# DebugBreakout_RevD.net
KiCad netlist of a schematic drawn in Altium Designer
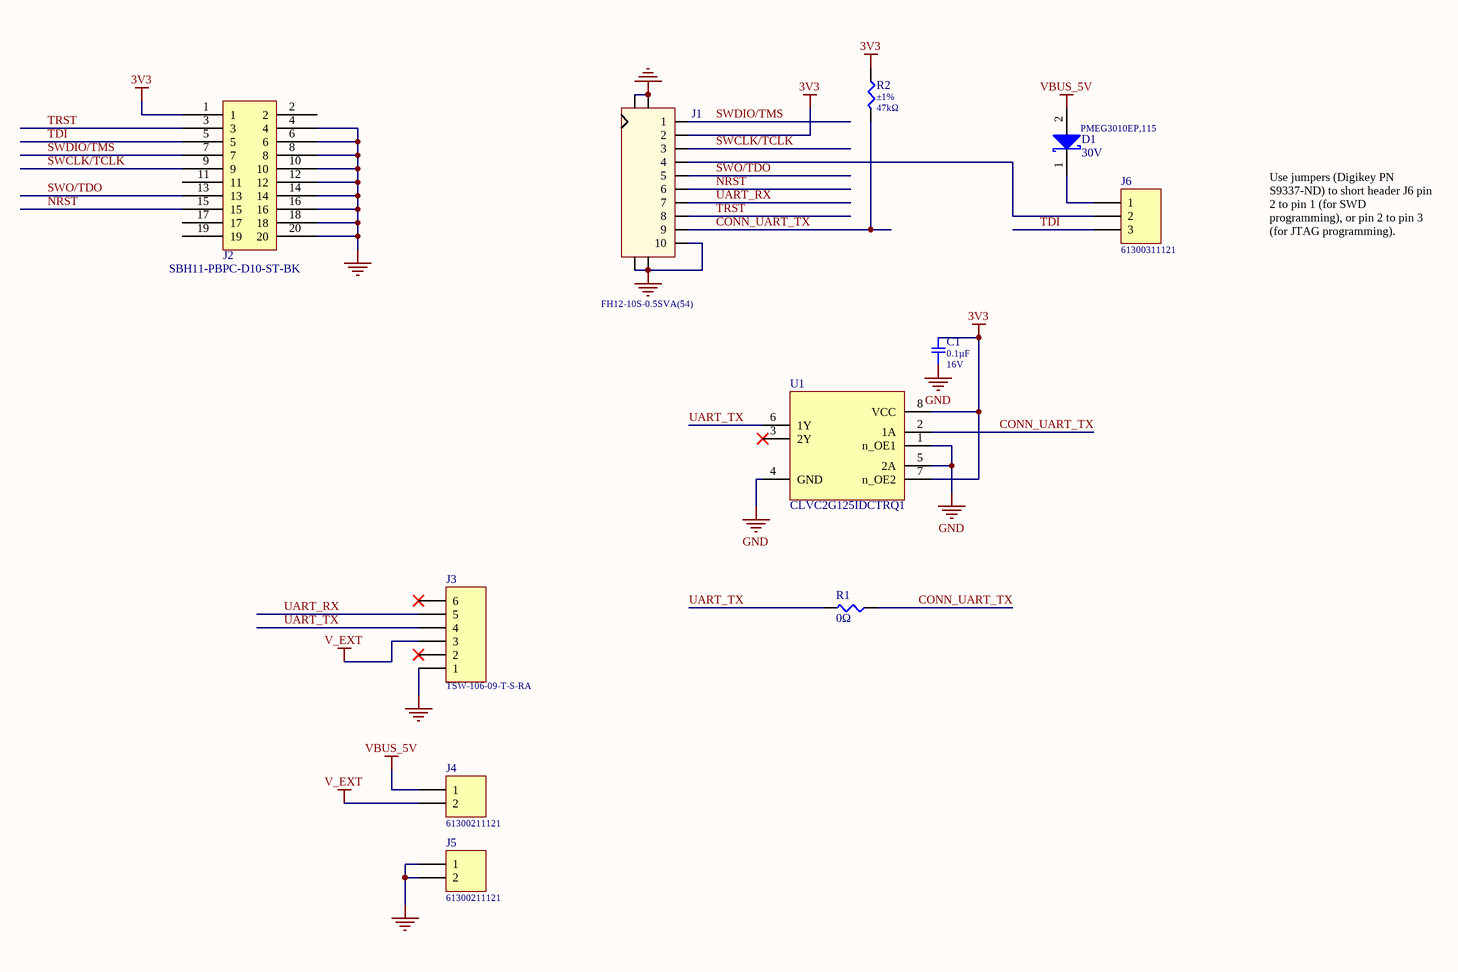
[diagram p0: DebugBreakout_RevD.SchDoc]

(export (version "E")
  (design (tool "Eeschema 10.0.6"))
  (components
    (comp (ref "C1")
      (value "0.1µF")
      (footprint "CAP-0402")
      (description "CAP CER 0.1UF 16V X7R 0402 5%")
      (fields
        (field (name "MANUFACTURER") "Murata")
        (field (name "MPN") "GRM155R71C104JA88D")
        (field (name "VOLTAGE RATING") "16V")
      )
      (libsource (lib "capacitors") (part "CAP-0.1uF-16V-0402"))
    )
    (comp (ref "D1")
      (value "PMEG3010EP,115")
      (footprint "DIODE-SOD128")
      (description "DIODE SCHOTTKY 30V 1A SOD128")
      (fields (field (name "BASE PART NUMBER") "PMEG3010") (field (name "REVERSE VOLTAGE") "30V"))
      (libsource (lib "diodes") (part "DIODE-SCHOTTKY-30V-1A-SOD128"))
    )
    (comp (ref "J1")
      (value "FH12-10S-0.5SVA(54)")
      (footprint "CONN-V-FPC-10P FH12-10S-0.5SVA(54)")
      (description "CONN FFC VERT 10POS 0.50MM SMD")
      (libsource (lib "msx") (part "CONN-V-FPC-10P-0.5MM"))
    )
    (comp (ref "J2")
      (value "SBH11-PBPC-D10-ST-BK")
      (footprint "HDR-V-2x10-KEYED")
      (description "CONN HEADER VERT 20POS 2.54MM")
      (libsource (lib "headers") (part "HDR-V-2x10-M"))
    )
    (comp (ref "J3")
      (value "TSW-106-09-T-S-RA")
      (footprint "HDR-RA-1X6")
      (description "Conn Unshrouded Header HDR 6 POS 2.54mm Solder RA Thru-Hole Automotive Bulk")
      (libsource (lib "headers") (part "HDR-RA-1X6-M"))
    )
    (comp (ref "J4")
      (value "61300211121")
      (footprint "HDR-V-1X2")
      (description "Header, 2-Pin, 0.1\"")
      (fields (field (name "MANUFACTURER") "Wurth Electronics") (field (name "PUBLISHER") "Altium Limited"))
      (libsource (lib "headers") (part "HDR-V-1X2-M"))
    )
    (comp (ref "J5")
      (value "61300211121")
      (footprint "HDR-V-1X2")
      (description "Header, 2-Pin, 0.1\"")
      (fields (field (name "MANUFACTURER") "Wurth Electronics") (field (name "PUBLISHER") "Altium Limited"))
      (libsource (lib "headers") (part "HDR-V-1X2-M"))
    )
    (comp (ref "J6")
      (value "61300311121")
      (footprint "HDR-V-1X3")
      (description "Header, 3-Pin, 0.1\"")
      (fields (field (name "MANUFACTURER") "Wurth Electronics") (field (name "PUBLISHER") "Altium Limited"))
      (libsource (lib "headers") (part "HDR-V-1X3-M"))
    )
    (comp (ref "R1")
      (value "0Ω")
      (footprint "RES-0402")
      (description "RES 0 OHM JUMPER 1/16W 0402")
      (fields
        (field (name "MANUFACTURER") "Yageo")
        (field (name "MANUFACTURER PART NUMBER") "RC0402FR-070RL")
      )
      (libsource (lib "resistors") (part "RES-0-0402"))
    )
    (comp (ref "R2")
      (value "47kΩ")
      (footprint "RES-0402")
      (description "RES SMD 47K OHM 1% 1/16W 0402")
      (fields (field (name "TOLERANCE") "±1%") (field (name "Comment") "RC0402FR-0747KL"))
      (libsource (lib "resistors") (part "RES-47K-0402"))
    )
    (comp (ref "U1")
      (value "CLVC2G125IDCTRQ1")
      (footprint "IC-MSOP-8P")
      (description "5.5 V SMT Dual Buffer Gate with 3-State Outputs - SM8")
      (libsource (lib "chagan") (part "IC-CLVC2G125I"))
    )
  )
  (nets
    (net (code "1") (name "/CONN_UART_TX") (class "Default")
      (node (ref "J1") (pin "9") (pinfunction "9_9") (pintype "passive"))
      (node (ref "R1") (pin "1") (pinfunction "1_1") (pintype "passive"))
      (node (ref "R2") (pin "2") (pinfunction "2_2") (pintype "passive"))
      (node (ref "U1") (pin "2") (pinfunction "1A_2") (pintype "passive"))
    )
    (net (code "2") (name "/NRST") (class "Default")
      (node (ref "J1") (pin "6") (pinfunction "6_6") (pintype "passive"))
      (node (ref "J2") (pin "15") (pinfunction "15_15") (pintype "power_in"))
    )
    (net (code "3") (name "/SWCLK{slash}TCLK") (class "Default")
      (node (ref "J1") (pin "3") (pinfunction "3_3") (pintype "passive"))
      (node (ref "J2") (pin "9") (pinfunction "9_9") (pintype "passive"))
    )
    (net (code "4") (name "/SWDIO{slash}TMS") (class "Default")
      (node (ref "J1") (pin "1") (pinfunction "1_1") (pintype "passive"))
      (node (ref "J2") (pin "7") (pinfunction "7_7") (pintype "passive"))
    )
    (net (code "5") (name "/SWO{slash}TDO") (class "Default")
      (node (ref "J1") (pin "5") (pinfunction "5_5") (pintype "passive"))
      (node (ref "J2") (pin "13") (pinfunction "13_13") (pintype "power_in"))
    )
    (net (code "6") (name "/TDI") (class "Default")
      (node (ref "J2") (pin "5") (pinfunction "5_5") (pintype "passive"))
      (node (ref "J6") (pin "3") (pinfunction "3_3") (pintype "passive"))
    )
    (net (code "7") (name "/TRST") (class "Default")
      (node (ref "J1") (pin "8") (pinfunction "8_8") (pintype "passive"))
      (node (ref "J2") (pin "3") (pinfunction "3_3") (pintype "passive"))
    )
    (net (code "8") (name "/UART_RX") (class "Default")
      (node (ref "J1") (pin "7") (pinfunction "7_7") (pintype "passive"))
      (node (ref "J3") (pin "5") (pinfunction "5_5") (pintype "passive"))
    )
    (net (code "9") (name "/UART_TX") (class "Default")
      (node (ref "J3") (pin "4") (pinfunction "4_4") (pintype "passive"))
      (node (ref "R1") (pin "2") (pinfunction "2_2") (pintype "passive"))
      (node (ref "U1") (pin "6") (pinfunction "1Y_6") (pintype "passive"))
    )
    (net (code "10") (name "3V3") (class "Default")
      (node (ref "C1") (pin "2") (pinfunction "2_2") (pintype "passive"))
      (node (ref "J1") (pin "2") (pinfunction "2_2") (pintype "passive"))
      (node (ref "J2") (pin "1") (pinfunction "1_1") (pintype "passive"))
      (node (ref "R2") (pin "1") (pinfunction "1_1") (pintype "passive"))
      (node (ref "U1") (pin "7") (pinfunction "n_OE2_7") (pintype "passive"))
      (node (ref "U1") (pin "8") (pinfunction "VCC_8") (pintype "passive"))
    )
    (net (code "11") (name "GND") (class "Default")
      (node (ref "C1") (pin "1") (pinfunction "1_1") (pintype "passive"))
      (node (ref "J1") (pin "10") (pinfunction "10_10") (pintype "passive"))
      (node (ref "J1") (pin "ME1") (pinfunction "ME1_ME1") (pintype "passive"))
      (node (ref "J1") (pin "ME2") (pinfunction "ME2_ME2") (pintype "passive"))
      (node (ref "J1") (pin "ME3") (pinfunction "ME3_ME3") (pintype "passive"))
      (node (ref "J1") (pin "ME4") (pinfunction "ME4_ME4") (pintype "passive"))
      (node (ref "J2") (pin "10") (pinfunction "10_10") (pintype "passive"))
      (node (ref "J2") (pin "12") (pinfunction "12_12") (pintype "power_in"))
      (node (ref "J2") (pin "14") (pinfunction "14_14") (pintype "power_in"))
      (node (ref "J2") (pin "16") (pinfunction "16_16") (pintype "power_in"))
      (node (ref "J2") (pin "18") (pinfunction "18_18") (pintype "power_in"))
      (node (ref "J2") (pin "20") (pinfunction "20_20") (pintype "power_in"))
      (node (ref "J2") (pin "4") (pinfunction "4_4") (pintype "passive"))
      (node (ref "J2") (pin "6") (pinfunction "6_6") (pintype "passive"))
      (node (ref "J2") (pin "8") (pinfunction "8_8") (pintype "passive"))
      (node (ref "J3") (pin "1") (pinfunction "1_1") (pintype "passive"))
      (node (ref "J5") (pin "1") (pinfunction "1_1") (pintype "passive"))
      (node (ref "J5") (pin "2") (pinfunction "2_2") (pintype "passive"))
      (node (ref "U1") (pin "1") (pinfunction "n_OE1_1") (pintype "passive"))
      (node (ref "U1") (pin "4") (pinfunction "GND_4") (pintype "passive"))
      (node (ref "U1") (pin "5") (pinfunction "2A_5") (pintype "passive"))
    )
    (net (code "12") (name "Net-(D1-K)") (class "Default")
      (node (ref "D1") (pin "1") (pinfunction "K_1") (pintype "passive"))
      (node (ref "J6") (pin "1") (pinfunction "1_1") (pintype "passive"))
    )
    (net (code "13") (name "Net-(J1-Pad4)") (class "Default")
      (node (ref "J1") (pin "4") (pinfunction "4_4") (pintype "passive"))
      (node (ref "J6") (pin "2") (pinfunction "2_2") (pintype "passive"))
    )
    (net (code "14") (name "VBUS_5V") (class "Default")
      (node (ref "D1") (pin "2") (pinfunction "A_2") (pintype "passive"))
      (node (ref "J4") (pin "1") (pinfunction "1_1") (pintype "passive"))
    )
    (net (code "15") (name "V_EXT") (class "Default")
      (node (ref "J3") (pin "3") (pinfunction "3_3") (pintype "passive"))
      (node (ref "J4") (pin "2") (pinfunction "2_2") (pintype "passive"))
    )
    (net (code "16") (name "unconnected-(J2-Pad2)") (class "Default")
      (node (ref "J2") (pin "2") (pinfunction "2_2") (pintype "passive"))
    )
    (net (code "17") (name "unconnected-(J2-Pad11)") (class "Default")
      (node (ref "J2") (pin "11") (pinfunction "11_11") (pintype "power_in"))
    )
    (net (code "18") (name "unconnected-(J2-Pad17)") (class "Default")
      (node (ref "J2") (pin "17") (pinfunction "17_17") (pintype "power_in"))
    )
    (net (code "19") (name "unconnected-(J2-Pad19)") (class "Default")
      (node (ref "J2") (pin "19") (pinfunction "19_19") (pintype "power_in"))
    )
    (net (code "20") (name "unconnected-(J3-Pad2)") (class "Default")
      (node (ref "J3") (pin "2") (pinfunction "2_2") (pintype "passive+no_connect"))
    )
    (net (code "21") (name "unconnected-(J3-Pad6)") (class "Default")
      (node (ref "J3") (pin "6") (pinfunction "6_6") (pintype "passive+no_connect"))
    )
    (net (code "22") (name "unconnected-(U1-2Y-Pad3)") (class "Default")
      (node (ref "U1") (pin "3") (pinfunction "2Y_3") (pintype "passive+no_connect"))
    )
  )
)
